# hvreg_feedback_3PS_ACDC.net
KiCad netlist of a schematic drawn in EAGLE
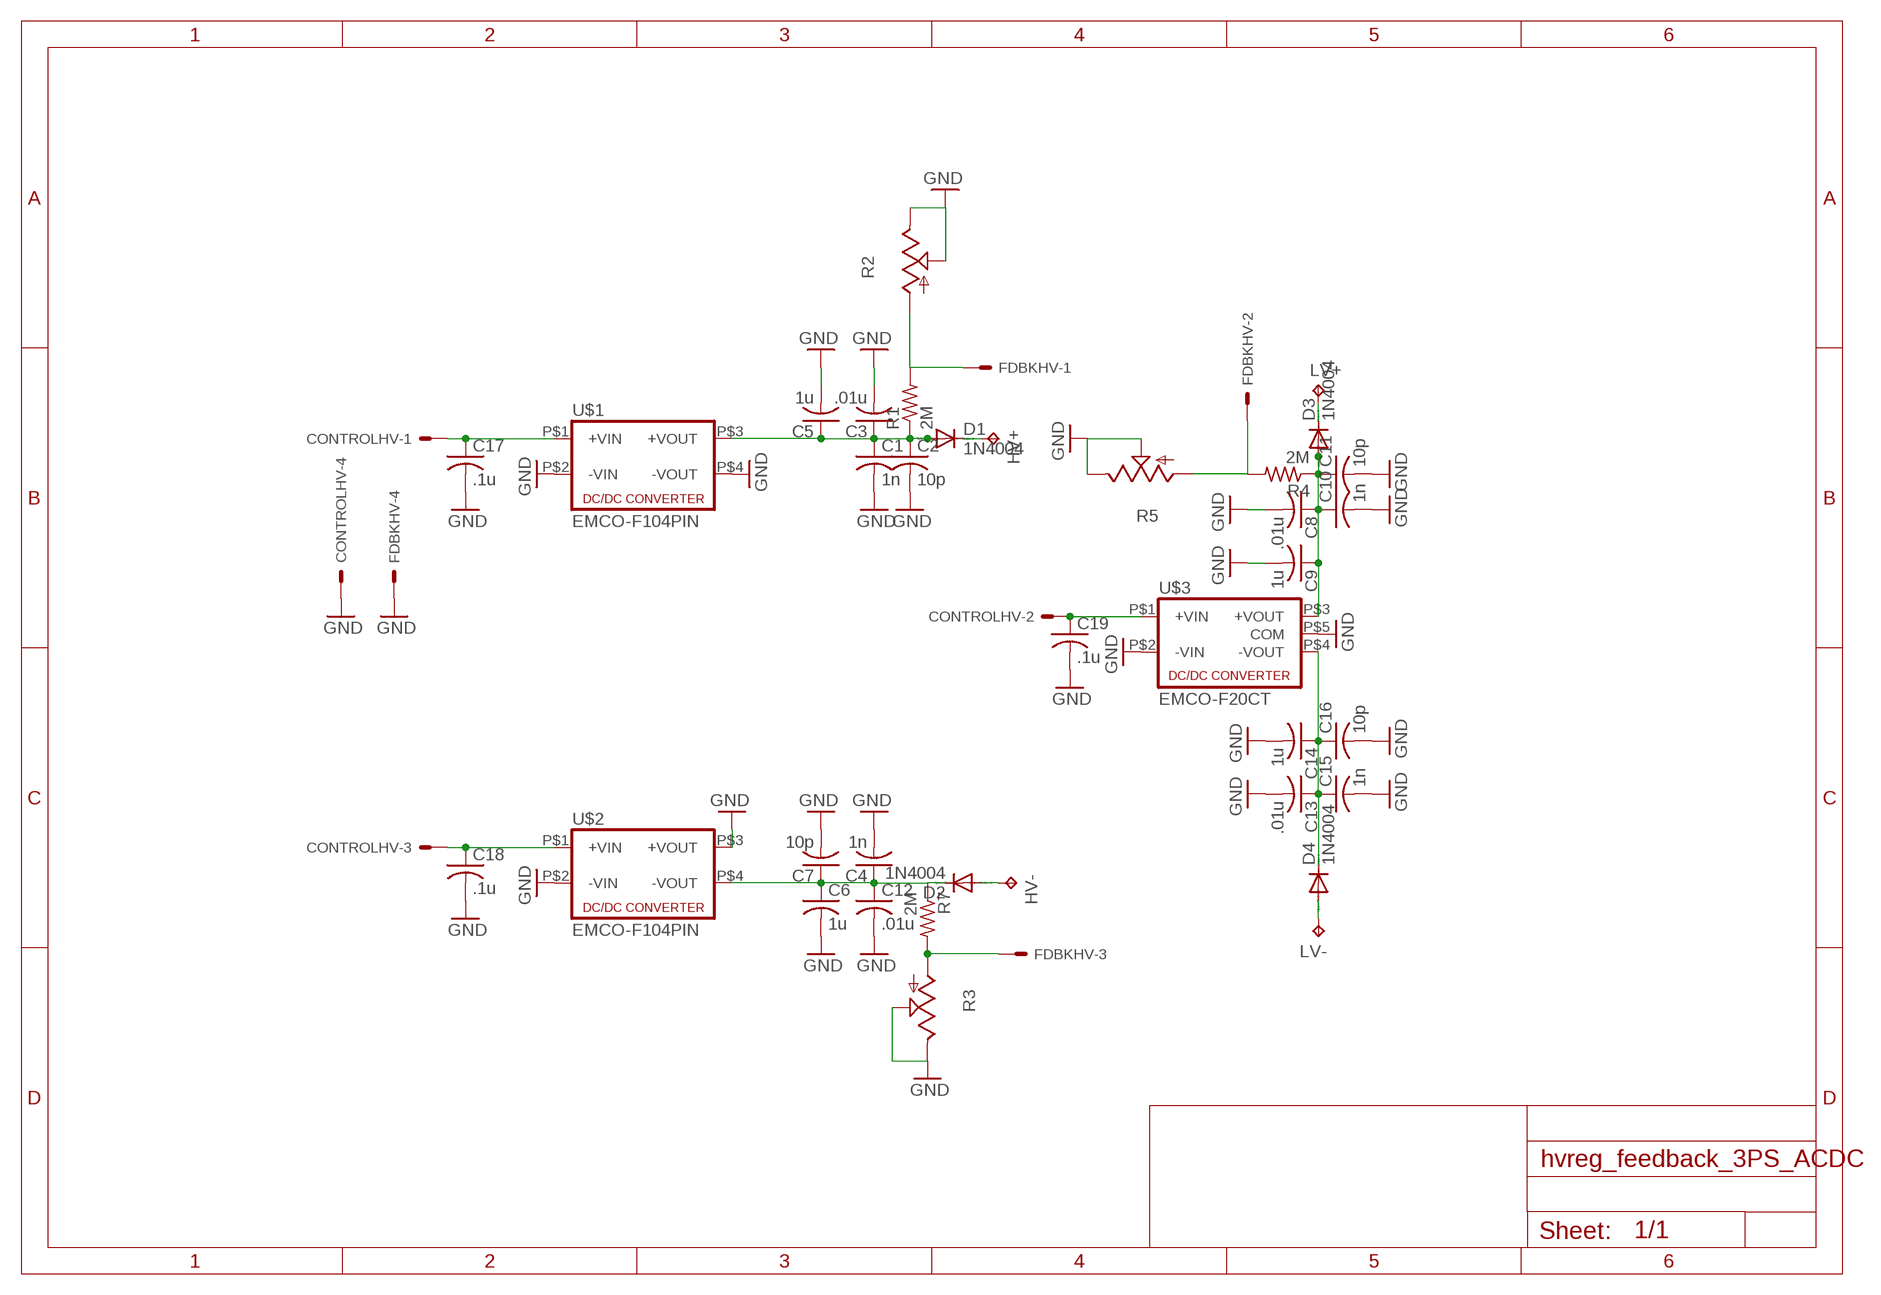
[diagram p0: schematic, sheet 1]

(export (version "E")
  (design (tool "Eeschema 10.0.6"))
  (components
    (comp (ref "C1")
      (value "1n")
      (footprint "eagle-import:C102-043X133")
      (libsource (lib "eagle-import") (part "C-US102-043X133"))
    )
    (comp (ref "C2")
      (value "10p")
      (footprint "eagle-import:C102-043X133")
      (libsource (lib "eagle-import") (part "C-US102-043X133"))
    )
    (comp (ref "C3")
      (value ".01u")
      (footprint "eagle-import:C102-043X133")
      (libsource (lib "eagle-import") (part "C-US102-043X133"))
    )
    (comp (ref "C4")
      (value "1n")
      (footprint "eagle-import:C102-043X133")
      (libsource (lib "eagle-import") (part "C-US102-043X133"))
    )
    (comp (ref "C5")
      (value "1u")
      (footprint "eagle-import:C275-205X316")
      (libsource (lib "eagle-import") (part "C-US275-205X316"))
    )
    (comp (ref "C6")
      (value "1u")
      (footprint "eagle-import:C275-205X316")
      (libsource (lib "eagle-import") (part "C-US275-205X316"))
    )
    (comp (ref "C7")
      (value "10p")
      (footprint "eagle-import:C102-043X133")
      (libsource (lib "eagle-import") (part "C-US102-043X133"))
    )
    (comp (ref "C8")
      (value ".01u")
      (footprint "eagle-import:C102-043X133")
      (libsource (lib "eagle-import") (part "C-US102-043X133"))
    )
    (comp (ref "C9")
      (value "1u")
      (footprint "eagle-import:C275-205X316")
      (libsource (lib "eagle-import") (part "C-US275-205X316"))
    )
    (comp (ref "C10")
      (value "1n")
      (footprint "eagle-import:C102-043X133")
      (libsource (lib "eagle-import") (part "C-US102-043X133"))
    )
    (comp (ref "C11")
      (value "10p")
      (footprint "eagle-import:C102-043X133")
      (libsource (lib "eagle-import") (part "C-US102-043X133"))
    )
    (comp (ref "C12")
      (value ".01u")
      (footprint "eagle-import:C102-043X133")
      (libsource (lib "eagle-import") (part "C-US102-043X133"))
    )
    (comp (ref "C13")
      (value ".01u")
      (footprint "eagle-import:C102-043X133")
      (libsource (lib "eagle-import") (part "C-US102-043X133"))
    )
    (comp (ref "C14")
      (value "1u")
      (footprint "eagle-import:C275-205X316")
      (libsource (lib "eagle-import") (part "C-US275-205X316"))
    )
    (comp (ref "C15")
      (value "1n")
      (footprint "eagle-import:C102-043X133")
      (libsource (lib "eagle-import") (part "C-US102-043X133"))
    )
    (comp (ref "C16")
      (value "10p")
      (footprint "eagle-import:C102-043X133")
      (libsource (lib "eagle-import") (part "C-US102-043X133"))
    )
    (comp (ref "C17")
      (value ".1u")
      (footprint "eagle-import:C102-043X133")
      (libsource (lib "eagle-import") (part "C-US102-043X133"))
    )
    (comp (ref "C18")
      (value ".1u")
      (footprint "eagle-import:C102-043X133")
      (libsource (lib "eagle-import") (part "C-US102-043X133"))
    )
    (comp (ref "C19")
      (value ".1u")
      (footprint "eagle-import:C102-043X133")
      (libsource (lib "eagle-import") (part "C-US102-043X133"))
    )
    (comp (ref "CONTROLHV")
      (value "KK-156-4")
      (footprint "eagle-import:KK-156-4")
      (libsource (lib "eagle-import") (part "KK-156-4"))
    )
    (comp (ref "D1")
      (value "1N4004")
      (footprint "eagle-import:DO41-10")
      (libsource (lib "eagle-import") (part "1N4004"))
    )
    (comp (ref "D2")
      (value "1N4004")
      (footprint "eagle-import:DO41-10")
      (libsource (lib "eagle-import") (part "1N4004"))
    )
    (comp (ref "D3")
      (value "1N4004")
      (footprint "eagle-import:DO41-10")
      (libsource (lib "eagle-import") (part "1N4004"))
    )
    (comp (ref "D4")
      (value "1N4004")
      (footprint "eagle-import:DO41-10")
      (libsource (lib "eagle-import") (part "1N4004"))
    )
    (comp (ref "FDBKHV")
      (value "KK-156-4")
      (footprint "eagle-import:KK-156-4")
      (libsource (lib "eagle-import") (part "KK-156-4"))
    )
    (comp (ref "HV+")
      (value "TPPAD1-20Y")
      (footprint "eagle-import:P1-20Y")
      (libsource (lib "eagle-import") (part "TPPAD1-20Y"))
    )
    (comp (ref "HV-")
      (value "TPPAD1-20Y")
      (footprint "eagle-import:P1-20Y")
      (libsource (lib "eagle-import") (part "TPPAD1-20Y"))
    )
    (comp (ref "LV+")
      (value "TPPAD1-20Y")
      (footprint "eagle-import:P1-20Y")
      (libsource (lib "eagle-import") (part "TPPAD1-20Y"))
    )
    (comp (ref "LV-")
      (value "TPPAD1-20Y")
      (footprint "eagle-import:P1-20Y")
      (libsource (lib "eagle-import") (part "TPPAD1-20Y"))
    )
    (comp (ref "R1")
      (value "2M")
      (footprint "eagle-import:P0613_15")
      (libsource (lib "eagle-import") (part "R-US_0613/15"))
    )
    (comp (ref "R2")
      (value "TRIM_US-B90P")
      (footprint "eagle-import:SP19L")
      (libsource (lib "eagle-import") (part "TRIM_US-B90P"))
    )
    (comp (ref "R3")
      (value "TRIM_US-B90P")
      (footprint "eagle-import:SP19L")
      (libsource (lib "eagle-import") (part "TRIM_US-B90P"))
    )
    (comp (ref "R4")
      (value "2M")
      (footprint "eagle-import:P0613_15")
      (libsource (lib "eagle-import") (part "R-US_0613/15"))
    )
    (comp (ref "R5")
      (value "TRIM_US-B90P")
      (footprint "eagle-import:SP19L")
      (libsource (lib "eagle-import") (part "TRIM_US-B90P"))
    )
    (comp (ref "R7")
      (value "2M")
      (footprint "eagle-import:P0613_15")
      (libsource (lib "eagle-import") (part "R-US_0613/15"))
    )
    (comp (ref "U$1")
      (value "EMCO-F104PIN")
      (footprint "eagle-import:EMCO-F")
      (libsource (lib "eagle-import") (part "EMCO-F104PIN"))
    )
    (comp (ref "U$2")
      (value "EMCO-F104PIN")
      (footprint "eagle-import:EMCO-F")
      (libsource (lib "eagle-import") (part "EMCO-F104PIN"))
    )
    (comp (ref "U$3")
      (value "EMCO-F20CT")
      (footprint "eagle-import:EMCO-F_CT")
      (libsource (lib "eagle-import") (part "EMCO-F20CT"))
    )
  )
  (nets
    (net (code "1") (name "GND") (class "Default")
      (node (ref "C1") (pin "2") (pinfunction "2_2") (pintype "passive"))
      (node (ref "C10") (pin "2") (pinfunction "2_2") (pintype "passive"))
      (node (ref "C11") (pin "2") (pinfunction "2_2") (pintype "passive"))
      (node (ref "C12") (pin "2") (pinfunction "2_2") (pintype "passive"))
      (node (ref "C13") (pin "2") (pinfunction "2_2") (pintype "passive"))
      (node (ref "C14") (pin "2") (pinfunction "2_2") (pintype "passive"))
      (node (ref "C15") (pin "2") (pinfunction "2_2") (pintype "passive"))
      (node (ref "C16") (pin "2") (pinfunction "2_2") (pintype "passive"))
      (node (ref "C17") (pin "2") (pinfunction "2_2") (pintype "passive"))
      (node (ref "C18") (pin "2") (pinfunction "2_2") (pintype "passive"))
      (node (ref "C19") (pin "2") (pinfunction "2_2") (pintype "passive"))
      (node (ref "C2") (pin "2") (pinfunction "2_2") (pintype "passive"))
      (node (ref "C3") (pin "2") (pinfunction "2_2") (pintype "passive"))
      (node (ref "C4") (pin "2") (pinfunction "2_2") (pintype "passive"))
      (node (ref "C5") (pin "2") (pinfunction "2_2") (pintype "passive"))
      (node (ref "C6") (pin "2") (pinfunction "2_2") (pintype "passive"))
      (node (ref "C7") (pin "2") (pinfunction "2_2") (pintype "passive"))
      (node (ref "C8") (pin "2") (pinfunction "2_2") (pintype "passive"))
      (node (ref "C9") (pin "2") (pinfunction "2_2") (pintype "passive"))
      (node (ref "CONTROLHV") (pin "4") (pinfunction "S_4") (pintype "passive"))
      (node (ref "FDBKHV") (pin "4") (pinfunction "S_4") (pintype "passive"))
      (node (ref "R2") (pin "E") (pinfunction "E_E") (pintype "passive"))
      (node (ref "R2") (pin "S") (pinfunction "S_S") (pintype "passive"))
      (node (ref "R3") (pin "E") (pinfunction "E_E") (pintype "passive"))
      (node (ref "R3") (pin "S") (pinfunction "S_S") (pintype "passive"))
      (node (ref "R5") (pin "E") (pinfunction "E_E") (pintype "passive"))
      (node (ref "R5") (pin "S") (pinfunction "S_S") (pintype "passive"))
      (node (ref "U$1") (pin "P$2") (pinfunction "-VIN_P$2") (pintype "passive"))
      (node (ref "U$1") (pin "P$4") (pinfunction "-VOUT_P$4") (pintype "passive"))
      (node (ref "U$2") (pin "P$2") (pinfunction "-VIN_P$2") (pintype "passive"))
      (node (ref "U$2") (pin "P$3") (pinfunction "+VOUT_P$3") (pintype "passive"))
      (node (ref "U$3") (pin "P$2") (pinfunction "-VIN_P$2") (pintype "passive"))
      (node (ref "U$3") (pin "P$5") (pinfunction "COM_P$5") (pintype "passive"))
    )
    (net (code "2") (name "Net-(CONTROLHVA-S)") (class "Default")
      (node (ref "C17") (pin "1") (pinfunction "1_1") (pintype "passive"))
      (node (ref "CONTROLHV") (pin "1") (pinfunction "S_1") (pintype "passive"))
      (node (ref "U$1") (pin "P$1") (pinfunction "+VIN_P$1") (pintype "passive"))
    )
    (net (code "3") (name "Net-(CONTROLHVB-S)") (class "Default")
      (node (ref "C19") (pin "1") (pinfunction "1_1") (pintype "passive"))
      (node (ref "CONTROLHV") (pin "2") (pinfunction "S_2") (pintype "passive"))
      (node (ref "U$3") (pin "P$1") (pinfunction "+VIN_P$1") (pintype "passive"))
    )
    (net (code "4") (name "Net-(CONTROLHVC-S)") (class "Default")
      (node (ref "C18") (pin "1") (pinfunction "1_1") (pintype "passive"))
      (node (ref "CONTROLHV") (pin "3") (pinfunction "S_3") (pintype "passive"))
      (node (ref "U$2") (pin "P$1") (pinfunction "+VIN_P$1") (pintype "passive"))
    )
    (net (code "5") (name "Net-(D1-PadC)") (class "Default")
      (node (ref "D1") (pin "C") (pinfunction "C_C") (pintype "passive"))
      (node (ref "HV+") (pin "TP") (pinfunction "TP_TP") (pintype "input"))
    )
    (net (code "6") (name "Net-(D2-PadA)") (class "Default")
      (node (ref "D2") (pin "A") (pinfunction "A_A") (pintype "passive"))
      (node (ref "HV-") (pin "TP") (pinfunction "TP_TP") (pintype "input"))
    )
    (net (code "7") (name "Net-(D3-PadC)") (class "Default")
      (node (ref "D3") (pin "C") (pinfunction "C_C") (pintype "passive"))
      (node (ref "LV+") (pin "TP") (pinfunction "TP_TP") (pintype "input"))
    )
    (net (code "8") (name "Net-(D4-PadA)") (class "Default")
      (node (ref "D4") (pin "A") (pinfunction "A_A") (pintype "passive"))
      (node (ref "LV-") (pin "TP") (pinfunction "TP_TP") (pintype "input"))
    )
    (net (code "9") (name "Net-(FDBKHVA-S)") (class "Default")
      (node (ref "FDBKHV") (pin "1") (pinfunction "S_1") (pintype "passive"))
      (node (ref "R1") (pin "2") (pinfunction "2_2") (pintype "passive"))
      (node (ref "R2") (pin "A") (pinfunction "A_A") (pintype "passive"))
    )
    (net (code "10") (name "Net-(FDBKHVB-S)") (class "Default")
      (node (ref "FDBKHV") (pin "2") (pinfunction "S_2") (pintype "passive"))
      (node (ref "R4") (pin "2") (pinfunction "2_2") (pintype "passive"))
      (node (ref "R5") (pin "A") (pinfunction "A_A") (pintype "passive"))
    )
    (net (code "11") (name "Net-(FDBKHVC-S)") (class "Default")
      (node (ref "FDBKHV") (pin "3") (pinfunction "S_3") (pintype "passive"))
      (node (ref "R3") (pin "A") (pinfunction "A_A") (pintype "passive"))
      (node (ref "R7") (pin "2") (pinfunction "2_2") (pintype "passive"))
    )
    (net (code "12") (name "Net-(U$1-+VOUT)") (class "Default")
      (node (ref "C1") (pin "1") (pinfunction "1_1") (pintype "passive"))
      (node (ref "C2") (pin "1") (pinfunction "1_1") (pintype "passive"))
      (node (ref "C3") (pin "1") (pinfunction "1_1") (pintype "passive"))
      (node (ref "C5") (pin "1") (pinfunction "1_1") (pintype "passive"))
      (node (ref "D1") (pin "A") (pinfunction "A_A") (pintype "passive"))
      (node (ref "R1") (pin "1") (pinfunction "1_1") (pintype "passive"))
      (node (ref "U$1") (pin "P$3") (pinfunction "+VOUT_P$3") (pintype "passive"))
    )
    (net (code "13") (name "Net-(U$2--VOUT)") (class "Default")
      (node (ref "C12") (pin "1") (pinfunction "1_1") (pintype "passive"))
      (node (ref "C4") (pin "1") (pinfunction "1_1") (pintype "passive"))
      (node (ref "C6") (pin "1") (pinfunction "1_1") (pintype "passive"))
      (node (ref "C7") (pin "1") (pinfunction "1_1") (pintype "passive"))
      (node (ref "D2") (pin "C") (pinfunction "C_C") (pintype "passive"))
      (node (ref "R7") (pin "1") (pinfunction "1_1") (pintype "passive"))
      (node (ref "U$2") (pin "P$4") (pinfunction "-VOUT_P$4") (pintype "passive"))
    )
    (net (code "14") (name "Net-(U$3-+VOUT)") (class "Default")
      (node (ref "C10") (pin "1") (pinfunction "1_1") (pintype "passive"))
      (node (ref "C11") (pin "1") (pinfunction "1_1") (pintype "passive"))
      (node (ref "C8") (pin "1") (pinfunction "1_1") (pintype "passive"))
      (node (ref "C9") (pin "1") (pinfunction "1_1") (pintype "passive"))
      (node (ref "D3") (pin "A") (pinfunction "A_A") (pintype "passive"))
      (node (ref "R4") (pin "1") (pinfunction "1_1") (pintype "passive"))
      (node (ref "U$3") (pin "P$3") (pinfunction "+VOUT_P$3") (pintype "passive"))
    )
    (net (code "15") (name "Net-(U$3--VOUT)") (class "Default")
      (node (ref "C13") (pin "1") (pinfunction "1_1") (pintype "passive"))
      (node (ref "C14") (pin "1") (pinfunction "1_1") (pintype "passive"))
      (node (ref "C15") (pin "1") (pinfunction "1_1") (pintype "passive"))
      (node (ref "C16") (pin "1") (pinfunction "1_1") (pintype "passive"))
      (node (ref "D4") (pin "C") (pinfunction "C_C") (pintype "passive"))
      (node (ref "U$3") (pin "P$4") (pinfunction "-VOUT_P$4") (pintype "passive"))
    )
  )
)
